# can.net
KiCad netlist of a schematic drawn in Altium Designer
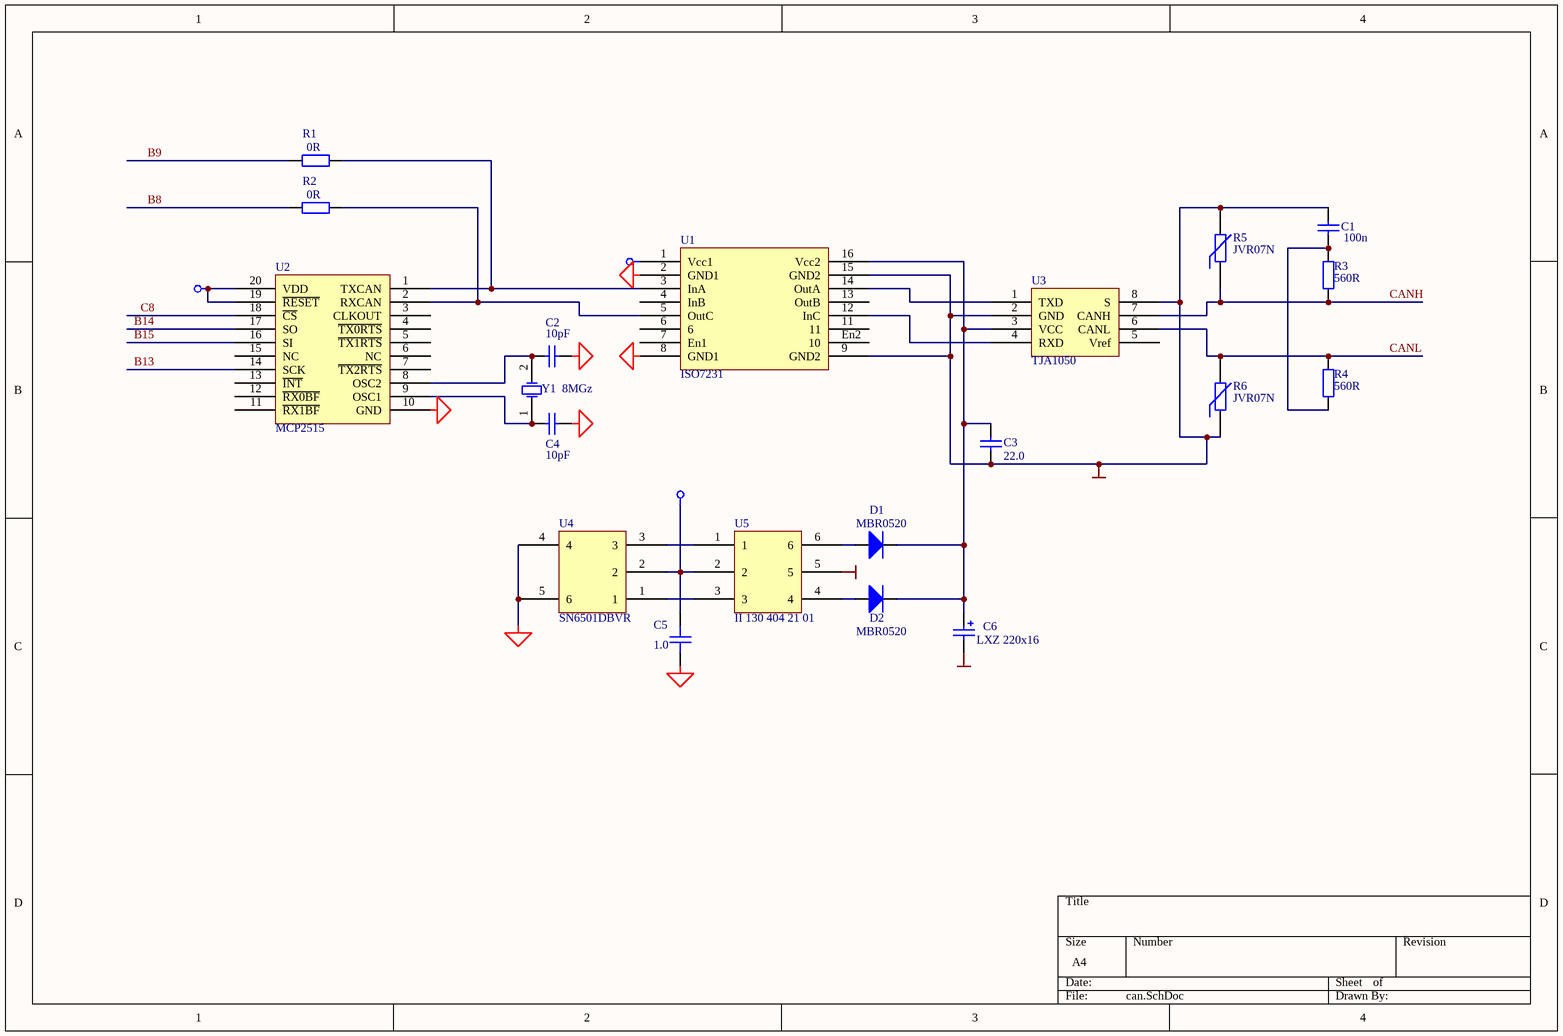
[diagram p0: can.SchDoc]

(export (version "E")
  (design (tool "Eeschema 10.0.6"))
  (components
    (comp (ref "C1")
      (value "100n")
      (footprint "_1206")
      (description "Capacitor (Semiconductor SIM Model)")
      (fields (field (name "MANUFACTURER") "Generic Components") (field (name "PUBLISHER") "Altium Limited"))
      (libsource (lib "Miscellaneous Devices") (part "Cap Semi"))
    )
    (comp (ref "C2")
      (value "10pF")
      (footprint "_1206")
      (description "Capacitor (Semiconductor SIM Model)")
      (fields
        (field (name "MANUFACTURER") "Generic Components")
        (field (name "ALTIUM_VALUE") "10pF")
        (field (name "PUBLISHER") "Altium Limited")
      )
      (libsource (lib "Miscellaneous Devices") (part "Cap Semi"))
    )
    (comp (ref "C3")
      (value "22.0")
      (footprint "_1206")
      (description "Capacitor (Semiconductor SIM Model)")
      (fields (field (name "MANUFACTURER") "Generic Components") (field (name "PUBLISHER") "Altium Limited"))
      (libsource (lib "Miscellaneous Devices") (part "Cap Semi"))
    )
    (comp (ref "C4")
      (value "10pF")
      (footprint "_1206")
      (description "Capacitor (Semiconductor SIM Model)")
      (fields
        (field (name "MANUFACTURER") "Generic Components")
        (field (name "ALTIUM_VALUE") "10pF")
        (field (name "PUBLISHER") "Altium Limited")
      )
      (libsource (lib "Miscellaneous Devices") (part "Cap Semi"))
    )
    (comp (ref "C5") (value "1.0") (footprint "_1206") (libsource (lib "C") (part "C_SM_1206")))
    (comp (ref "C6")
      (value "LXZ 220x16")
      (footprint "el3")
      (description "Polarized Capacitor (Radial)")
      (fields (field (name "MANUFACTURER") "Generic Components") (field (name "PUBLISHER") "Altium Limited"))
      (libsource (lib "PAL") (part "Cap Pol1"))
    )
    (comp (ref "D1")
      (value "MBR0520")
      (footprint "_1206d")
      (description "Default Diode")
      (fields (field (name "MANUFACTURER") "Generic Components") (field (name "PUBLISHER") "Altium Limited"))
      (libsource (lib "PAL") (part "Diode"))
    )
    (comp (ref "D2")
      (value "MBR0520")
      (footprint "_1206d")
      (description "Default Diode")
      (fields (field (name "MANUFACTURER") "Generic Components") (field (name "PUBLISHER") "Altium Limited"))
      (libsource (lib "PAL") (part "Diode"))
    )
    (comp (ref "R1")
      (value "0R")
      (footprint "_1206")
      (description "Resistor")
      (fields (field (name "MANUFACTURER") "Generic Components") (field (name "PUBLISHER") "Altium Limited"))
      (libsource (lib "Miscellaneous Devices") (part "Res2"))
    )
    (comp (ref "R2")
      (value "0R")
      (footprint "_1206")
      (description "Resistor")
      (fields (field (name "MANUFACTURER") "Generic Components") (field (name "PUBLISHER") "Altium Limited"))
      (libsource (lib "Miscellaneous Devices") (part "Res2"))
    )
    (comp (ref "R3")
      (value "560R")
      (footprint "_1206")
      (description "Resistor")
      (fields (field (name "MANUFACTURER") "Generic Components") (field (name "PUBLISHER") "Altium Limited"))
      (libsource (lib "") (part "Res2_1"))
    )
    (comp (ref "R4")
      (value "560R")
      (footprint "_1206")
      (description "Resistor")
      (fields (field (name "MANUFACTURER") "Generic Components") (field (name "PUBLISHER") "Altium Limited"))
      (libsource (lib "") (part "Res2_1"))
    )
    (comp (ref "R5")
      (value "JVR07N")
      (footprint "JVR07N")
      (description "Varistor (Voltage-Sensitive Resistor)")
      (fields (field (name "MANUFACTURER") "Generic Components") (field (name "PUBLISHER") "Altium Limited"))
      (libsource (lib "Miscellaneous Devices") (part "Res Varistor"))
    )
    (comp (ref "R6")
      (value "JVR07N")
      (footprint "JVR07N")
      (description "Varistor (Voltage-Sensitive Resistor)")
      (fields (field (name "MANUFACTURER") "Generic Components") (field (name "PUBLISHER") "Altium Limited"))
      (libsource (lib "Miscellaneous Devices") (part "Res Varistor"))
    )
    (comp (ref "U1") (value "ISO7231") (footprint "SO-G16/D10.4") (libsource (lib "PAL") (part "ISO7231")))
    (comp (ref "U2")
      (value "MCP2515")
      (footprint "TSSO6X6-G20/D6.6")
      (libsource (lib "PAL") (part "MCP2515"))
    )
    (comp (ref "U3") (value "TJA1050") (footprint "SO-G8/D5") (libsource (lib "PAL") (part "TJA1050")))
    (comp (ref "U4") (value "SN6501DBVR") (footprint "SO-G5/P.95") (libsource (lib "") (part "PIN6_1")))
    (comp (ref "U5")
      (value "II 130 404 21 01")
      (footprint "II1304042101")
      (libsource (lib "CHIP") (part "PIN6"))
    )
    (comp (ref "Y1")
      (value "8MGz")
      (footprint "QWARZ1")
      (description "Crystal Oscillator")
      (fields (field (name "MANUFACTURER") "Generic Components") (field (name "PUBLISHER") "Altium Limited"))
      (libsource (lib "Miscellaneous Devices") (part "XTAL"))
    )
  )
  (nets
    (net (code "1") (name "+3v3") (class "Default")
      (node (ref "U2") (pin "19") (pinfunction "~{RESET}_19") (pintype "passive"))
      (node (ref "U2") (pin "20") (pinfunction "VDD_20") (pintype "passive"))
    )
    (net (code "2") (name "+5v") (class "Default")
      (node (ref "C5") (pin "2") (pinfunction "2_2") (pintype "passive"))
      (node (ref "U1") (pin "1") (pinfunction "Vcc1_1") (pintype "passive"))
      (node (ref "U4") (pin "2") (pinfunction "2_2") (pintype "passive"))
      (node (ref "U5") (pin "2") (pinfunction "2_2") (pintype "passive"))
    )
    (net (code "3") (name "/B8") (class "Default")
      (node (ref "R2") (pin "1") (pinfunction "1_1") (pintype "passive"))
    )
    (net (code "4") (name "/B9") (class "Default")
      (node (ref "R1") (pin "1") (pinfunction "1_1") (pintype "passive"))
    )
    (net (code "5") (name "/B13") (class "Default")
      (node (ref "U2") (pin "14") (pinfunction "SCK_14") (pintype "passive"))
    )
    (net (code "6") (name "/B14") (class "Default")
      (node (ref "U2") (pin "17") (pinfunction "SO_17") (pintype "passive"))
    )
    (net (code "7") (name "/B15") (class "Default")
      (node (ref "U2") (pin "16") (pinfunction "SI_16") (pintype "passive"))
    )
    (net (code "8") (name "/C8") (class "Default")
      (node (ref "U2") (pin "18") (pinfunction "~{CS}_18") (pintype "passive"))
    )
    (net (code "9") (name "/CANH") (class "Default")
      (node (ref "R3") (pin "1") (pinfunction "1_1") (pintype "passive"))
      (node (ref "R5") (pin "1") (pinfunction "1_1") (pintype "passive"))
      (node (ref "U3") (pin "7") (pinfunction "CANH_7") (pintype "passive"))
    )
    (net (code "10") (name "/CANL") (class "Default")
      (node (ref "R4") (pin "2") (pinfunction "2_2") (pintype "passive"))
      (node (ref "R6") (pin "2") (pinfunction "2_2") (pintype "passive"))
      (node (ref "U3") (pin "6") (pinfunction "CANL_6") (pintype "passive"))
    )
    (net (code "11") (name "GND") (class "Default")
      (node (ref "C2") (pin "1") (pinfunction "1_1") (pintype "passive"))
      (node (ref "C4") (pin "1") (pinfunction "1_1") (pintype "passive"))
      (node (ref "C5") (pin "1") (pinfunction "1_1") (pintype "passive"))
      (node (ref "U1") (pin "2") (pinfunction "GND1_2") (pintype "passive"))
      (node (ref "U1") (pin "8") (pinfunction "GND1_8") (pintype "passive"))
      (node (ref "U2") (pin "10") (pinfunction "GND_10") (pintype "passive"))
      (node (ref "U4") (pin "4") (pinfunction "4_4") (pintype "passive"))
      (node (ref "U4") (pin "5") (pinfunction "6_5") (pintype "passive"))
    )
    (net (code "12") (name "GND_CAN") (class "Default")
      (node (ref "C1") (pin "2") (pinfunction "2_2") (pintype "passive"))
      (node (ref "C3") (pin "2") (pinfunction "2_2") (pintype "passive"))
      (node (ref "C6") (pin "2") (pinfunction "2_2") (pintype "passive"))
      (node (ref "R5") (pin "2") (pinfunction "2_2") (pintype "passive"))
      (node (ref "R6") (pin "1") (pinfunction "1_1") (pintype "passive"))
      (node (ref "U1") (pin "15") (pinfunction "GND2_15") (pintype "passive"))
      (node (ref "U1") (pin "9") (pinfunction "GND2_9") (pintype "passive"))
      (node (ref "U3") (pin "2") (pinfunction "GND_2") (pintype "passive"))
      (node (ref "U3") (pin "8") (pinfunction "S_8") (pintype "passive"))
      (node (ref "U5") (pin "5") (pinfunction "5_5") (pintype "passive"))
    )
    (net (code "13") (name "Net-(C1-Pad1)") (class "Default")
      (node (ref "C1") (pin "1") (pinfunction "1_1") (pintype "passive"))
      (node (ref "R3") (pin "2") (pinfunction "2_2") (pintype "passive"))
      (node (ref "R4") (pin "1") (pinfunction "1_1") (pintype "passive"))
    )
    (net (code "14") (name "Net-(D1-A)") (class "Default")
      (node (ref "D1") (pin "1") (pinfunction "A_1") (pintype "passive"))
      (node (ref "U5") (pin "6") (pinfunction "6_6") (pintype "passive"))
    )
    (net (code "15") (name "Net-(D1-K)") (class "Default")
      (node (ref "C3") (pin "1") (pinfunction "1_1") (pintype "passive"))
      (node (ref "C6") (pin "1") (pinfunction "1_1") (pintype "passive"))
      (node (ref "D1") (pin "2") (pinfunction "K_2") (pintype "passive"))
      (node (ref "D2") (pin "2") (pinfunction "K_2") (pintype "passive"))
      (node (ref "U1") (pin "16") (pinfunction "Vcc2_16") (pintype "passive"))
      (node (ref "U3") (pin "3") (pinfunction "VCC_3") (pintype "passive"))
    )
    (net (code "16") (name "Net-(D2-A)") (class "Default")
      (node (ref "D2") (pin "1") (pinfunction "A_1") (pintype "passive"))
      (node (ref "U5") (pin "4") (pinfunction "4_4") (pintype "passive"))
    )
    (net (code "17") (name "Net-(U1-InA)") (class "Default")
      (node (ref "R1") (pin "2") (pinfunction "2_2") (pintype "passive"))
      (node (ref "U1") (pin "3") (pinfunction "InA_3") (pintype "passive"))
      (node (ref "U2") (pin "1") (pinfunction "TXCAN_1") (pintype "passive"))
    )
    (net (code "18") (name "Net-(U1-InC)") (class "Default")
      (node (ref "U1") (pin "12") (pinfunction "InC_12") (pintype "passive"))
      (node (ref "U3") (pin "4") (pinfunction "RXD_4") (pintype "passive"))
    )
    (net (code "19") (name "Net-(U1-OutA)") (class "Default")
      (node (ref "U1") (pin "14") (pinfunction "OutA_14") (pintype "passive"))
      (node (ref "U3") (pin "1") (pinfunction "TXD_1") (pintype "passive"))
    )
    (net (code "20") (name "Net-(U1-OutC)") (class "Default")
      (node (ref "R2") (pin "2") (pinfunction "2_2") (pintype "passive"))
      (node (ref "U1") (pin "5") (pinfunction "OutC_5") (pintype "passive"))
      (node (ref "U2") (pin "2") (pinfunction "RXCAN_2") (pintype "passive"))
    )
    (net (code "21") (name "Net-(U2-OSC1)") (class "Default")
      (node (ref "C4") (pin "2") (pinfunction "2_2") (pintype "passive"))
      (node (ref "U2") (pin "9") (pinfunction "OSC1_9") (pintype "passive"))
      (node (ref "Y1") (pin "1") (pinfunction "OSC1_1") (pintype "passive"))
    )
    (net (code "22") (name "Net-(U2-OSC2)") (class "Default")
      (node (ref "C2") (pin "2") (pinfunction "2_2") (pintype "passive"))
      (node (ref "U2") (pin "8") (pinfunction "OSC2_8") (pintype "passive"))
      (node (ref "Y1") (pin "2") (pinfunction "OSC2_2") (pintype "passive"))
    )
    (net (code "23") (name "Net-(U4-Pad1)") (class "Default")
      (node (ref "U4") (pin "1") (pinfunction "1_1") (pintype "passive"))
      (node (ref "U5") (pin "3") (pinfunction "3_3") (pintype "passive"))
    )
    (net (code "24") (name "Net-(U4-Pad3)") (class "Default")
      (node (ref "U4") (pin "3") (pinfunction "3_3") (pintype "passive"))
      (node (ref "U5") (pin "1") (pinfunction "1_1") (pintype "passive"))
    )
    (net (code "25") (name "unconnected-(U1-10-PadEn2)") (class "Default")
      (node (ref "U1") (pin "En2") (pinfunction "10_En2") (pintype "passive"))
    )
    (net (code "26") (name "unconnected-(U1-En1-Pad7)") (class "Default")
      (node (ref "U1") (pin "7") (pinfunction "En1_7") (pintype "passive"))
    )
    (net (code "27") (name "unconnected-(U1-InB-Pad4)") (class "Default")
      (node (ref "U1") (pin "4") (pinfunction "InB_4") (pintype "passive"))
    )
    (net (code "28") (name "unconnected-(U1-OutB-Pad13)") (class "Default")
      (node (ref "U1") (pin "13") (pinfunction "OutB_13") (pintype "passive"))
    )
    (net (code "29") (name "unconnected-(U1-Pad6)") (class "Default")
      (node (ref "U1") (pin "6") (pinfunction "6_6") (pintype "passive"))
    )
    (net (code "30") (name "unconnected-(U1-Pad11)") (class "Default")
      (node (ref "U1") (pin "11") (pinfunction "11_11") (pintype "passive"))
    )
    (net (code "31") (name "unconnected-(U2-CLKOUT-Pad3)") (class "Default")
      (node (ref "U2") (pin "3") (pinfunction "CLKOUT_3") (pintype "passive"))
    )
    (net (code "32") (name "unconnected-(U2-NC-Pad6)") (class "Default")
      (node (ref "U2") (pin "6") (pinfunction "NC_6") (pintype "passive"))
    )
    (net (code "33") (name "unconnected-(U2-NC-Pad15)") (class "Default")
      (node (ref "U2") (pin "15") (pinfunction "NC_15") (pintype "passive"))
    )
    (net (code "34") (name "unconnected-(U2-~{INT}-Pad13)") (class "Default")
      (node (ref "U2") (pin "13") (pinfunction "~{INT}_13") (pintype "passive"))
    )
    (net (code "35") (name "unconnected-(U2-~{RX0BF}-Pad12)") (class "Default")
      (node (ref "U2") (pin "12") (pinfunction "~{RX0BF}_12") (pintype "passive"))
    )
    (net (code "36") (name "unconnected-(U2-~{RX1BF}-Pad11)") (class "Default")
      (node (ref "U2") (pin "11") (pinfunction "~{RX1BF}_11") (pintype "passive"))
    )
    (net (code "37") (name "unconnected-(U2-~{TX0RTS}-Pad4)") (class "Default")
      (node (ref "U2") (pin "4") (pinfunction "~{TX0RTS}_4") (pintype "passive"))
    )
    (net (code "38") (name "unconnected-(U2-~{TX1RTS}-Pad5)") (class "Default")
      (node (ref "U2") (pin "5") (pinfunction "~{TX1RTS}_5") (pintype "passive"))
    )
    (net (code "39") (name "unconnected-(U2-~{TX2RTS}-Pad7)") (class "Default")
      (node (ref "U2") (pin "7") (pinfunction "~{TX2RTS}_7") (pintype "passive"))
    )
    (net (code "40") (name "unconnected-(U3-Vref-Pad5)") (class "Default")
      (node (ref "U3") (pin "5") (pinfunction "Vref_5") (pintype "passive"))
    )
    (net (code "41") (name "unconnected-(U4-5-Pad6)") (class "Default")
      (node (ref "U4") (pin "6") (pinfunction "5_6") (pintype "passive"))
    )
  )
)
